# Rwanda_Sensor_Breakout.net
KiCad netlist of a schematic drawn in EAGLE
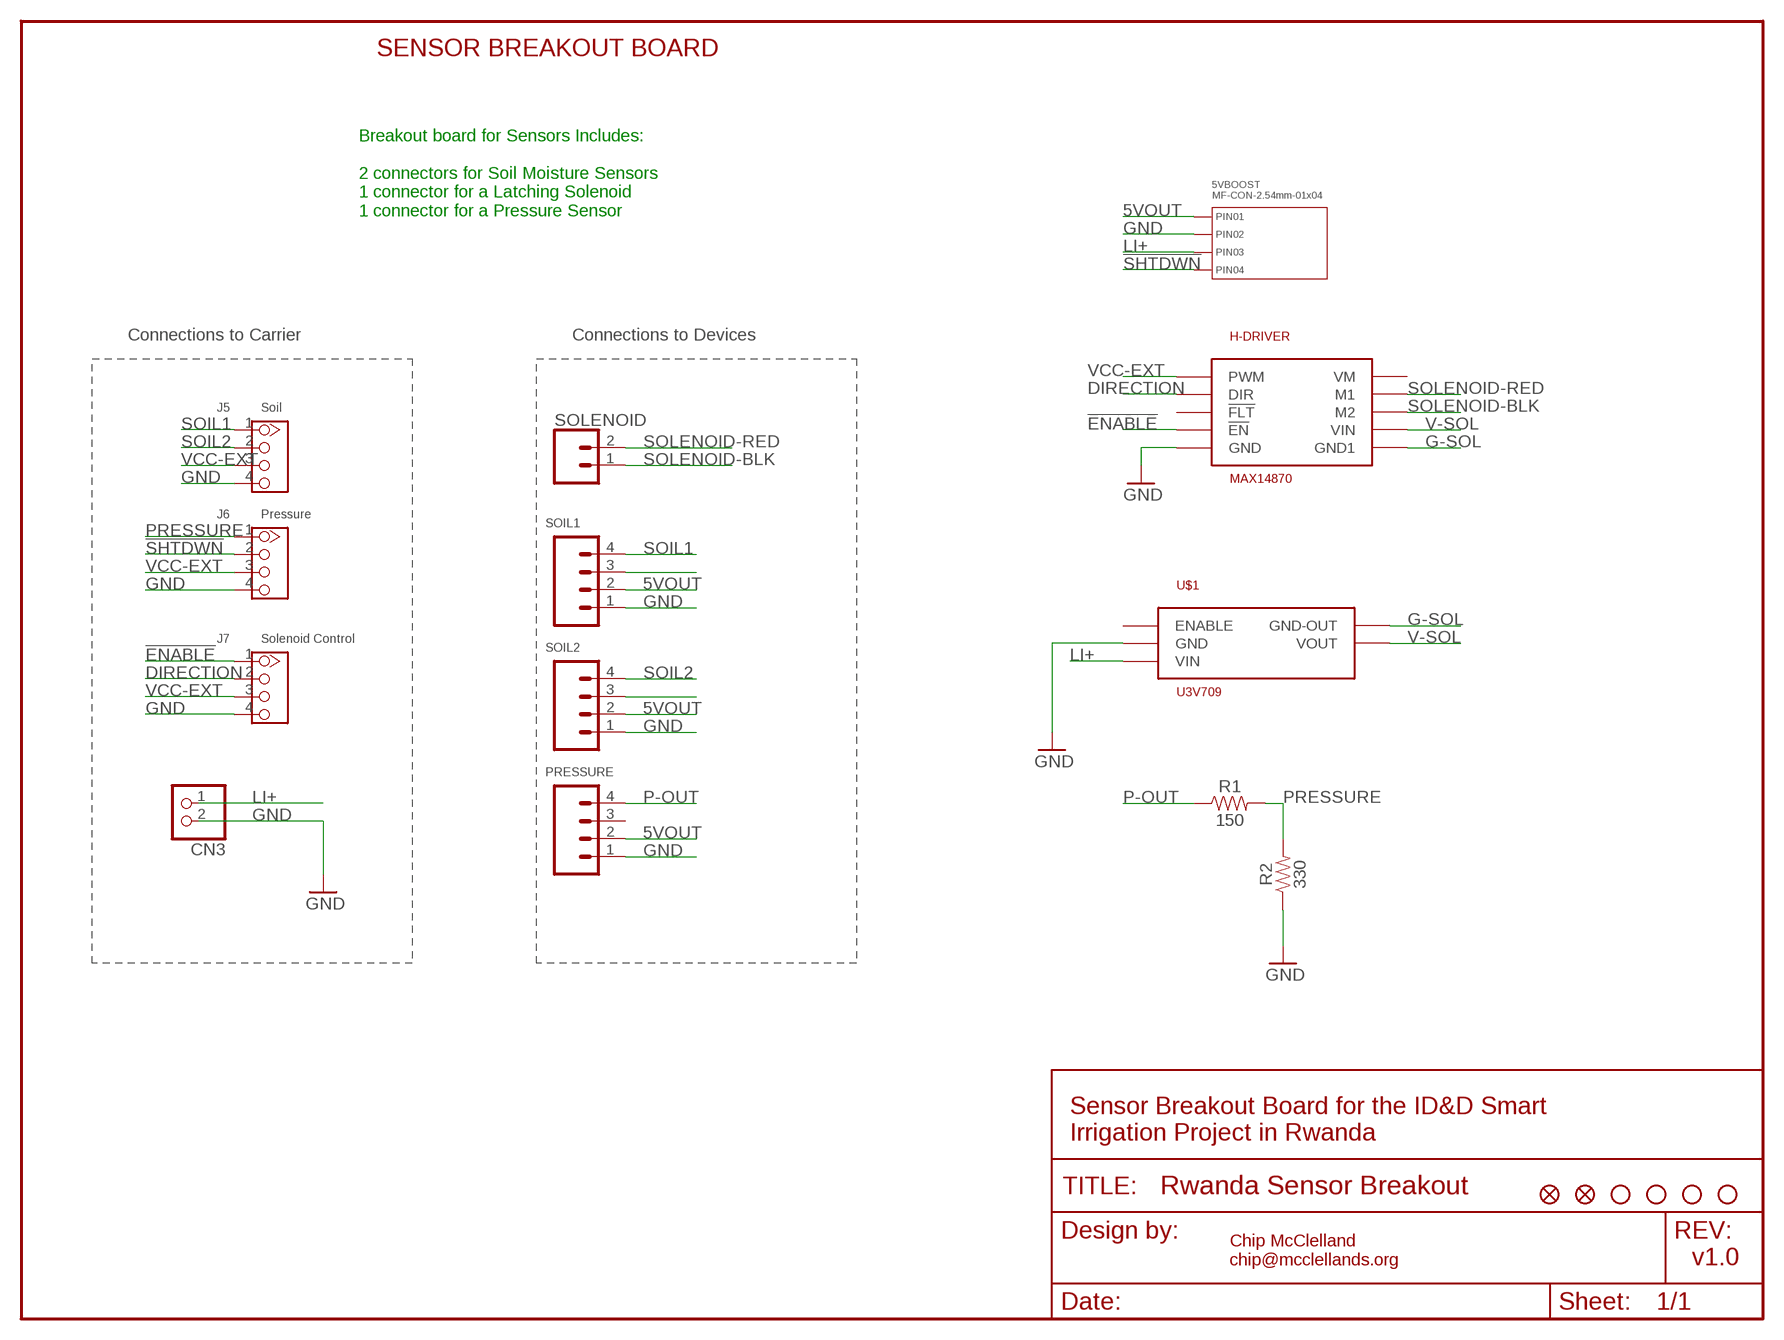
[diagram p0: schematic, sheet 1]

(export (version "E")
  (design (tool "Eeschema 10.0.6"))
  (components
    (comp (ref "5VBOOST")
      (value "MF-CON-2.54mm-01x04")
      (footprint "eagle-import:PTH_2.54MM_01X04")
      (fields (field (name "HOUSEPART") "YES"))
      (libsource (lib "eagle-import") (part "U1V11F5_PTH_2.54MM"))
    )
    (comp (ref "CN3")
      (value "JST_2PIN-SMT-RA")
      (footprint "eagle-import:JST-PH-2-SMT-RA")
      (libsource (lib "eagle-import") (part "JST_2PIN-SMT-RA"))
    )
    (comp (ref "FD1")
      (value "FIDUCIALUFIDUCIAL")
      (footprint "eagle-import:FIDUCIAL-MICRO")
      (libsource (lib "eagle-import") (part "FIDUCIALUFIDUCIAL"))
    )
    (comp (ref "FD2")
      (value "FIDUCIALUFIDUCIAL")
      (footprint "eagle-import:FIDUCIAL-MICRO")
      (libsource (lib "eagle-import") (part "FIDUCIALUFIDUCIAL"))
    )
    (comp (ref "FRAME1")
      (value "FRAME-LETTER")
      (footprint "eagle-import:CREATIVE_COMMONS")
      (fields (field (name "POPULATE") "0"))
      (libsource (lib "eagle-import") (part "FRAME-LETTER"))
    )
    (comp (ref "H-DRIVER")
      (value "MAX14870")
      (footprint "eagle-import:MAX14870-BREAKOUT")
      (libsource (lib "eagle-import") (part "MAX14870"))
    )
    (comp (ref "J5")
      (value "Soil")
      (footprint "eagle-import:HW4-2.0")
      (libsource (lib "eagle-import") (part "GROVE-CONNECTOR-DIP(4P-2.0)"))
    )
    (comp (ref "J6")
      (value "Pressure")
      (footprint "eagle-import:HW4-2.0")
      (libsource (lib "eagle-import") (part "GROVE-CONNECTOR-DIP(4P-2.0)"))
    )
    (comp (ref "J7")
      (value "Solenoid Control")
      (footprint "eagle-import:HW4-2.0")
      (libsource (lib "eagle-import") (part "GROVE-CONNECTOR-DIP(4P-2.0)"))
    )
    (comp (ref "JP3")
      (value "STAND-OFF")
      (footprint "eagle-import:STAND-OFF")
      (libsource (lib "eagle-import") (part "STAND-OFF"))
    )
    (comp (ref "JP4")
      (value "STAND-OFF")
      (footprint "eagle-import:STAND-OFF")
      (libsource (lib "eagle-import") (part "STAND-OFF"))
    )
    (comp (ref "JP5")
      (value "STAND-OFF")
      (footprint "eagle-import:STAND-OFF")
      (libsource (lib "eagle-import") (part "STAND-OFF"))
    )
    (comp (ref "JP6")
      (value "STAND-OFF")
      (footprint "eagle-import:STAND-OFF")
      (libsource (lib "eagle-import") (part "STAND-OFF"))
    )
    (comp (ref "PRESSURE")
      (value "Soil")
      (footprint "eagle-import:SCREWTERMINAL-3.5MM-4")
      (libsource (lib "eagle-import") (part "CONN_04SCREW"))
    )
    (comp (ref "R1")
      (value "150")
      (footprint "eagle-import:0805")
      (libsource (lib "eagle-import") (part "0.3OHM-0805-1/8W-1%"))
    )
    (comp (ref "R2")
      (value "330")
      (footprint "eagle-import:0805")
      (libsource (lib "eagle-import") (part "0.3OHM-0805-1/8W-1%"))
    )
    (comp (ref "SOIL1")
      (value "Soil")
      (footprint "eagle-import:SCREWTERMINAL-3.5MM-4")
      (libsource (lib "eagle-import") (part "CONN_04SCREW"))
    )
    (comp (ref "SOIL2")
      (value "Soil")
      (footprint "eagle-import:SCREWTERMINAL-3.5MM-4")
      (libsource (lib "eagle-import") (part "CONN_04SCREW"))
    )
    (comp (ref "SOLENOID")
      (value "CONN_025MM")
      (footprint "eagle-import:SCREWTERMINAL-5MM-2")
      (libsource (lib "eagle-import") (part "CONN_025MM"))
    )
    (comp (ref "U$1")
      (value "U3V709")
      (footprint "eagle-import:U3V70X-BREAKOUT")
      (libsource (lib "eagle-import") (part "U3V709"))
    )
  )
  (nets
    (net (code "1") (name "/5VOUT") (class "Default")
      (node (ref "5VBOOST") (pin "P$1") (pinfunction "PIN1_P$1") (pintype "bidirectional"))
      (node (ref "PRESSURE") (pin "2") (pinfunction "2_2") (pintype "passive"))
      (node (ref "SOIL1") (pin "2") (pinfunction "2_2") (pintype "passive"))
      (node (ref "SOIL2") (pin "2") (pinfunction "2_2") (pintype "passive"))
    )
    (net (code "2") (name "/DIRECTION") (class "Default")
      (node (ref "H-DRIVER") (pin "P$2") (pinfunction "DIR_P$2") (pintype "bidirectional"))
      (node (ref "J7") (pin "2") (pinfunction "2_2") (pintype "bidirectional"))
    )
    (net (code "3") (name "/G-SOL") (class "Default")
      (node (ref "H-DRIVER") (pin "P$6") (pinfunction "GND1_P$6") (pintype "bidirectional"))
      (node (ref "U$1") (pin "GOUT") (pinfunction "GND-OUT_GOUT") (pintype "bidirectional"))
      (node (ref "U$1") (pin "GOUT1") (pinfunction "GND-OUT_GOUT1") (pintype "bidirectional"))
    )
    (net (code "4") (name "/LI+") (class "Default")
      (node (ref "5VBOOST") (pin "P$3") (pinfunction "PIN3_P$3") (pintype "bidirectional"))
      (node (ref "CN3") (pin "1") (pinfunction "2_1") (pintype "passive"))
      (node (ref "U$1") (pin "VIN") (pinfunction "VIN_VIN") (pintype "bidirectional"))
      (node (ref "U$1") (pin "VIN1") (pinfunction "VIN_VIN1") (pintype "bidirectional"))
    )
    (net (code "5") (name "/P-OUT") (class "Default")
      (node (ref "PRESSURE") (pin "4") (pinfunction "4_4") (pintype "passive"))
      (node (ref "R1") (pin "1") (pinfunction "1_1") (pintype "passive"))
    )
    (net (code "6") (name "/PRESSURE") (class "Default")
      (node (ref "J6") (pin "1") (pinfunction "1_1") (pintype "bidirectional"))
      (node (ref "R1") (pin "2") (pinfunction "2_2") (pintype "passive"))
      (node (ref "R2") (pin "2") (pinfunction "2_2") (pintype "passive"))
    )
    (net (code "7") (name "/SOIL1") (class "Default")
      (node (ref "J5") (pin "1") (pinfunction "1_1") (pintype "bidirectional"))
      (node (ref "SOIL1") (pin "4") (pinfunction "4_4") (pintype "passive"))
    )
    (net (code "8") (name "/SOIL2") (class "Default")
      (node (ref "J5") (pin "2") (pinfunction "2_2") (pintype "bidirectional"))
      (node (ref "SOIL2") (pin "4") (pinfunction "4_4") (pintype "passive"))
    )
    (net (code "9") (name "/SOLENOID-BLK") (class "Default")
      (node (ref "H-DRIVER") (pin "P$8") (pinfunction "M2_P$8") (pintype "bidirectional"))
      (node (ref "SOLENOID") (pin "1") (pinfunction "1_1") (pintype "passive"))
    )
    (net (code "10") (name "/SOLENOID-RED") (class "Default")
      (node (ref "H-DRIVER") (pin "P$9") (pinfunction "M1_P$9") (pintype "bidirectional"))
      (node (ref "SOLENOID") (pin "2") (pinfunction "2_2") (pintype "passive"))
    )
    (net (code "11") (name "/V-SOL") (class "Default")
      (node (ref "H-DRIVER") (pin "P$7") (pinfunction "VIN_P$7") (pintype "bidirectional"))
      (node (ref "U$1") (pin "VOUT") (pinfunction "VOUT_VOUT") (pintype "bidirectional"))
      (node (ref "U$1") (pin "VOUT1") (pinfunction "VOUT_VOUT1") (pintype "bidirectional"))
    )
    (net (code "12") (name "/VCC-EXT") (class "Default")
      (node (ref "H-DRIVER") (pin "P$1") (pinfunction "PWM_P$1") (pintype "bidirectional"))
      (node (ref "J5") (pin "3") (pinfunction "3_3") (pintype "bidirectional"))
      (node (ref "J6") (pin "3") (pinfunction "3_3") (pintype "bidirectional"))
      (node (ref "J7") (pin "3") (pinfunction "3_3") (pintype "bidirectional"))
    )
    (net (code "13") (name "/~{ENABLE}") (class "Default")
      (node (ref "H-DRIVER") (pin "P$4") (pinfunction "~{EN}_P$4") (pintype "bidirectional"))
      (node (ref "J7") (pin "1") (pinfunction "1_1") (pintype "bidirectional"))
    )
    (net (code "14") (name "/~{SHTDWN}") (class "Default")
      (node (ref "5VBOOST") (pin "P$4") (pinfunction "PIN4_P$4") (pintype "bidirectional"))
      (node (ref "J6") (pin "2") (pinfunction "2_2") (pintype "bidirectional"))
    )
    (net (code "15") (name "GND") (class "Default")
      (node (ref "5VBOOST") (pin "P$2") (pinfunction "PIN2_P$2") (pintype "bidirectional"))
      (node (ref "CN3") (pin "2") (pinfunction "1_2") (pintype "passive"))
      (node (ref "H-DRIVER") (pin "P$5") (pinfunction "GND_P$5") (pintype "bidirectional"))
      (node (ref "J5") (pin "4") (pinfunction "4_4") (pintype "bidirectional"))
      (node (ref "J6") (pin "4") (pinfunction "4_4") (pintype "bidirectional"))
      (node (ref "J7") (pin "4") (pinfunction "4_4") (pintype "bidirectional"))
      (node (ref "PRESSURE") (pin "1") (pinfunction "1_1") (pintype "passive"))
      (node (ref "R2") (pin "1") (pinfunction "1_1") (pintype "passive"))
      (node (ref "SOIL1") (pin "1") (pinfunction "1_1") (pintype "passive"))
      (node (ref "SOIL2") (pin "1") (pinfunction "1_1") (pintype "passive"))
      (node (ref "U$1") (pin "GIN") (pinfunction "GND_GIN") (pintype "bidirectional"))
      (node (ref "U$1") (pin "GIN1") (pinfunction "GND_GIN1") (pintype "bidirectional"))
    )
    (net (code "16") (name "unconnected-(H-DRIVER-VM-PadP$10)") (class "Default")
      (node (ref "H-DRIVER") (pin "P$10") (pinfunction "VM_P$10") (pintype "bidirectional"))
    )
    (net (code "17") (name "unconnected-(H-DRIVER-~{FLT}-PadP$3)") (class "Default")
      (node (ref "H-DRIVER") (pin "P$3") (pinfunction "~{FLT}_P$3") (pintype "bidirectional"))
    )
    (net (code "18") (name "unconnected-(PRESSURE-Pad3)") (class "Default")
      (node (ref "PRESSURE") (pin "3") (pinfunction "3_3") (pintype "passive"))
    )
    (net (code "19") (name "unconnected-(SOIL1-Pad3)") (class "Default")
      (node (ref "SOIL1") (pin "3") (pinfunction "3_3") (pintype "passive"))
    )
    (net (code "20") (name "unconnected-(SOIL2-Pad3)") (class "Default")
      (node (ref "SOIL2") (pin "3") (pinfunction "3_3") (pintype "passive"))
    )
    (net (code "21") (name "unconnected-(U$1-PadENABLE)") (class "Default")
      (node (ref "U$1") (pin "ENABLE") (pinfunction "ENABLE_ENABLE") (pintype "bidirectional"))
    )
  )
)
